# stm32devboard_f103c6.net
KiCad netlist of a schematic drawn in EasyEDA Pro
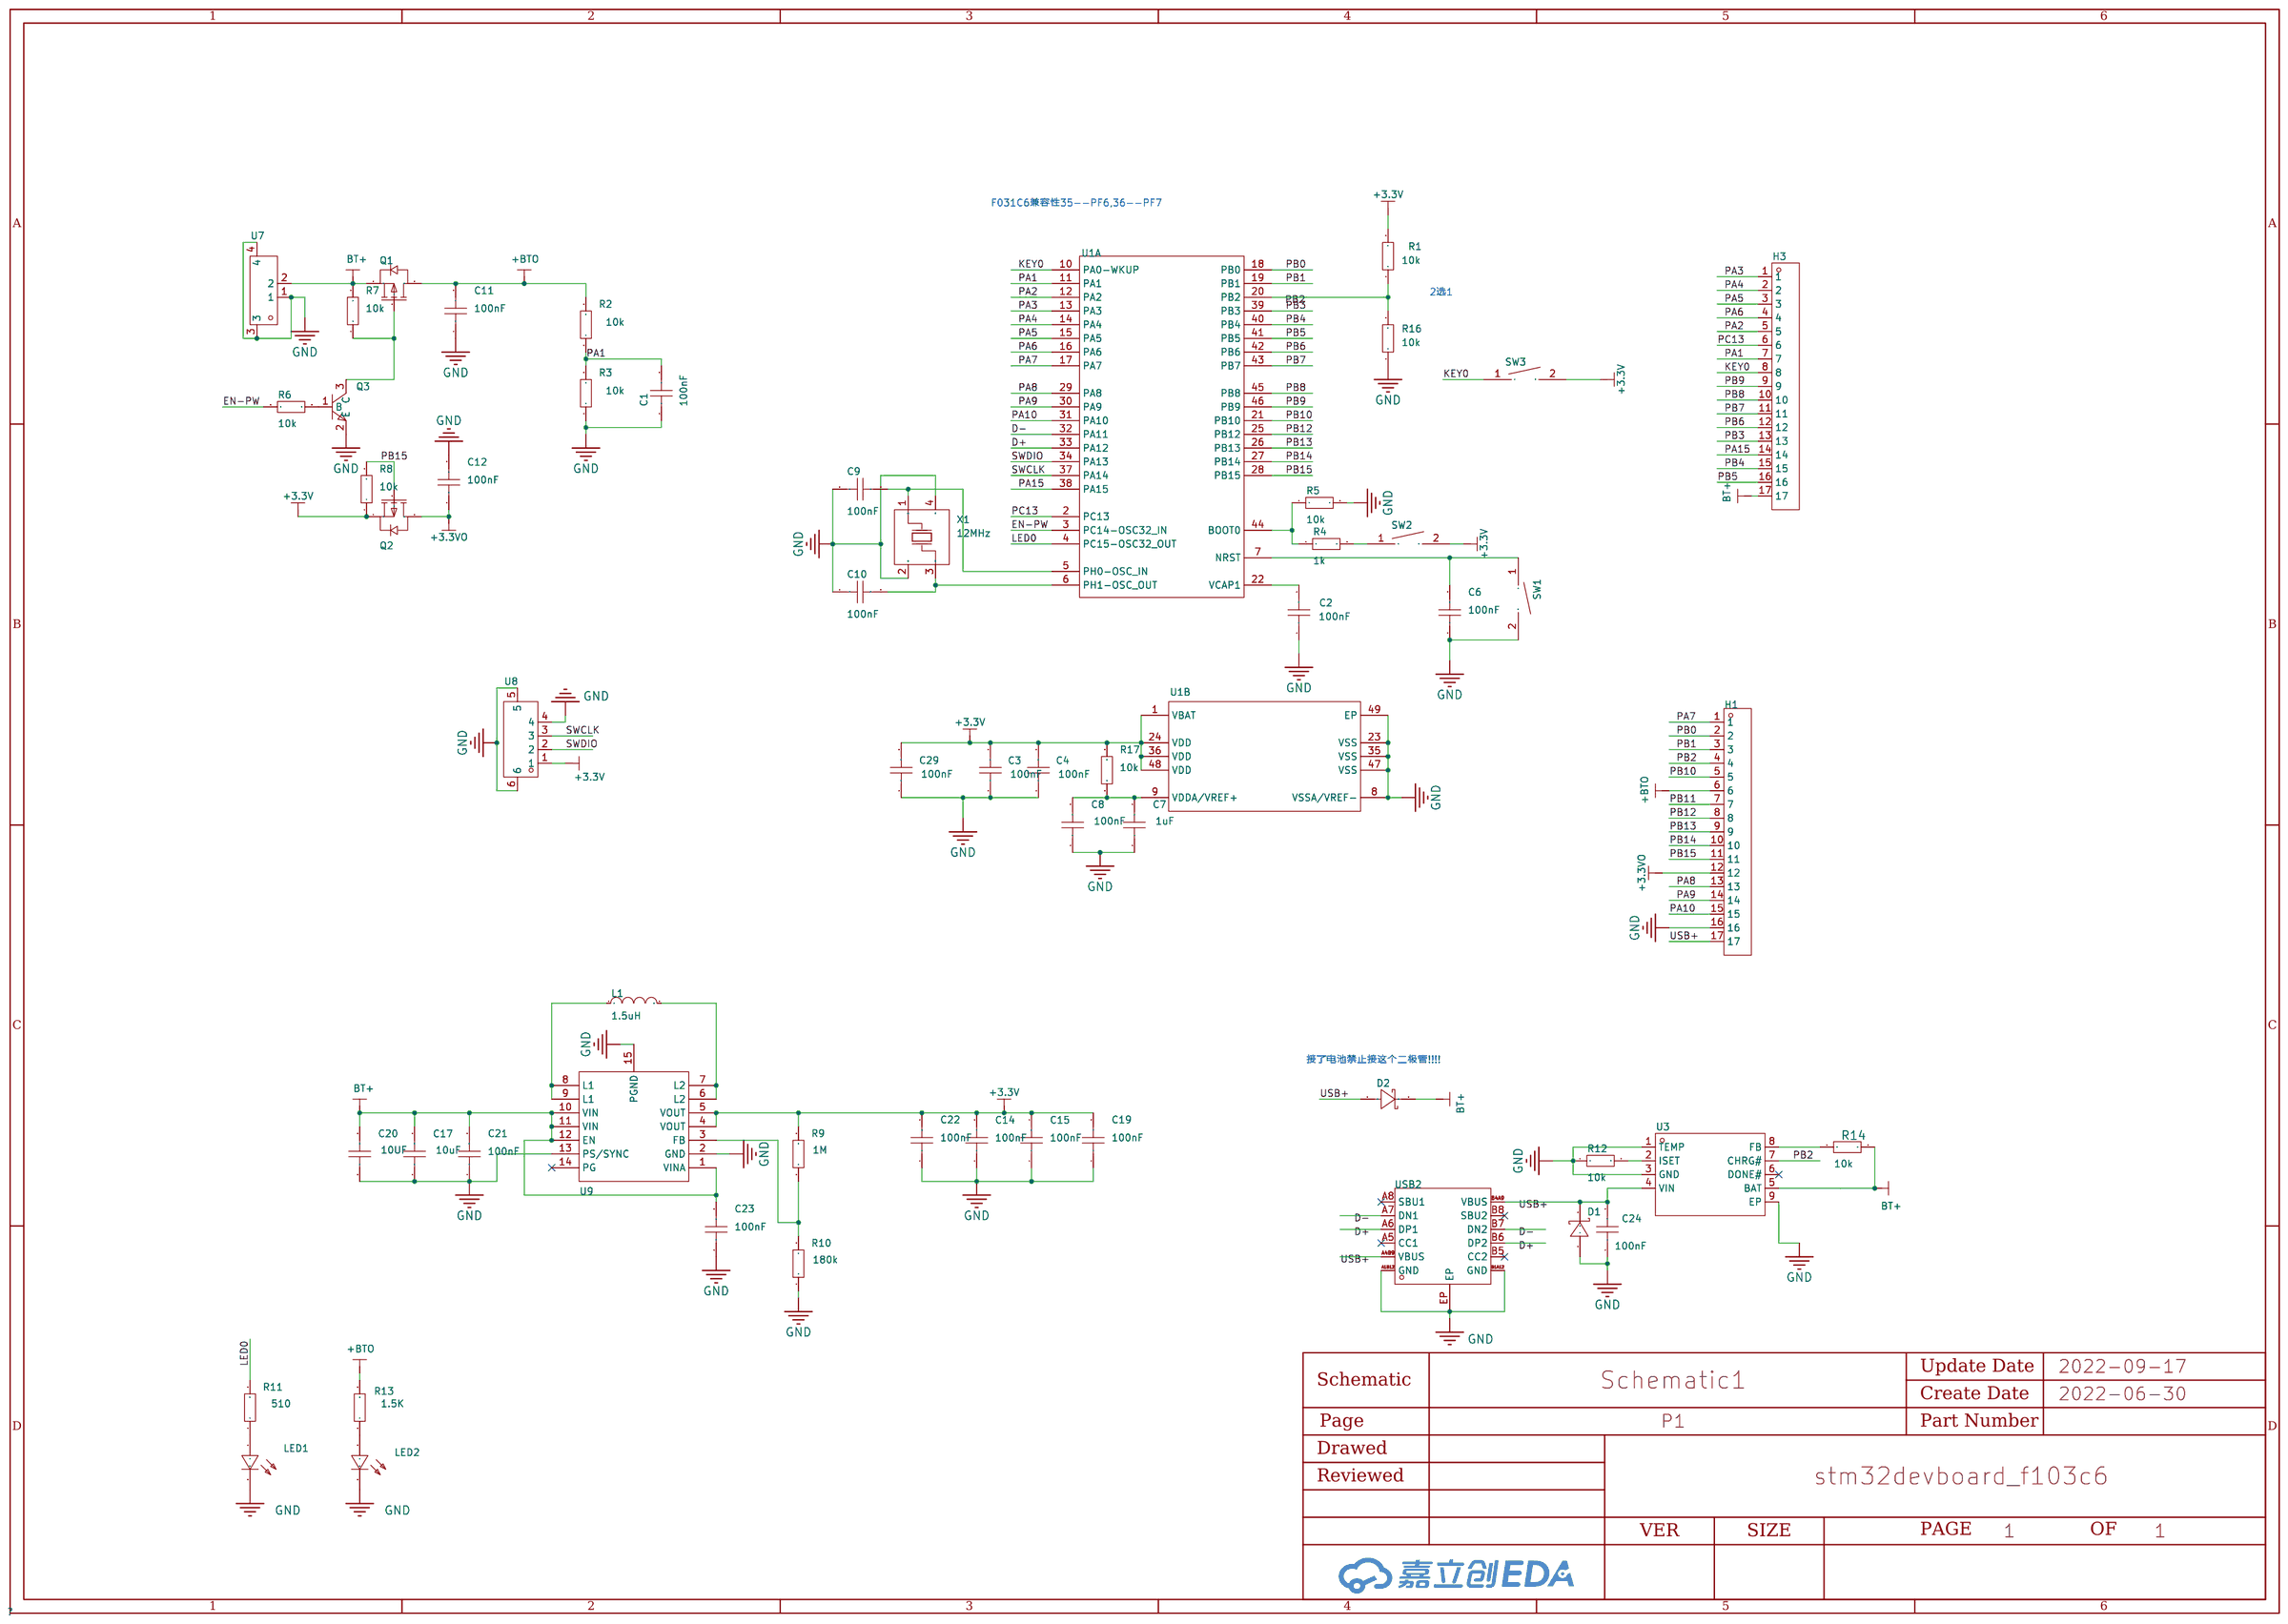
[diagram p0: schematic sheet]

(export (version "E")
  (design (tool "Eeschema 10.0.6"))
  (components
    (comp (ref "C1")
      (value "100nF")
      (footprint "easyedapro:C0402")
      (description "容值:100nF;精度:±10%;额定电压:25V;温度系数:X7R;")
      (fields (field (name "Manufacturer Part") "FN15X104K250PNG") (field (name "Manufacturer") "PSA(信昌电陶)"))
      (libsource (lib "easyedapro") (part "FN15X104K250PNG"))
    )
    (comp (ref "C2")
      (value "100nF")
      (footprint "easyedapro:C0603")
      (description "容值:100nF;精度:±10%;额定电压:50V;温度系数:X7R;")
      (fields
        (field (name "Manufacturer Part") "CC0603KRX7R9BB104")
        (field (name "Manufacturer") "YAGEO(国巨)")
      )
      (libsource (lib "easyedapro") (part "CC0603KRX7R9BB104"))
    )
    (comp (ref "C3")
      (value "100nF")
      (footprint "easyedapro:C0603")
      (description "容值:100nF;精度:±10%;额定电压:50V;温度系数:X7R;")
      (fields
        (field (name "Manufacturer Part") "CC0603KRX7R9BB104")
        (field (name "Manufacturer") "YAGEO(国巨)")
      )
      (libsource (lib "easyedapro") (part "CC0603KRX7R9BB104"))
    )
    (comp (ref "C4")
      (value "100nF")
      (footprint "easyedapro:C0603")
      (description "容值:100nF;精度:±10%;额定电压:50V;温度系数:X7R;")
      (fields
        (field (name "Manufacturer Part") "CC0603KRX7R9BB104")
        (field (name "Manufacturer") "YAGEO(国巨)")
      )
      (libsource (lib "easyedapro") (part "CC0603KRX7R9BB104"))
    )
    (comp (ref "C6")
      (value "100nF")
      (footprint "easyedapro:C0603")
      (description "容值:100nF;精度:±10%;额定电压:50V;温度系数:X7R;")
      (fields
        (field (name "Manufacturer Part") "CC0603KRX7R9BB104")
        (field (name "Manufacturer") "YAGEO(国巨)")
      )
      (libsource (lib "easyedapro") (part "CC0603KRX7R9BB104"))
    )
    (comp (ref "C7")
      (value "1uF")
      (footprint "easyedapro:C0603")
      (description "容值:100nF;精度:±10%;额定电压:50V;温度系数:X7R;")
      (fields
        (field (name "Manufacturer Part") "CC0603KRX7R9BB104")
        (field (name "Manufacturer") "YAGEO(国巨)")
      )
      (libsource (lib "easyedapro") (part "CC0603KRX7R9BB104"))
    )
    (comp (ref "C8")
      (value "100nF")
      (footprint "easyedapro:C0603")
      (description "容值:100nF;精度:±10%;额定电压:50V;温度系数:X7R;")
      (fields
        (field (name "Manufacturer Part") "CC0603KRX7R9BB104")
        (field (name "Manufacturer") "YAGEO(国巨)")
      )
      (libsource (lib "easyedapro") (part "CC0603KRX7R9BB104"))
    )
    (comp (ref "C9")
      (value "100nF")
      (footprint "easyedapro:C0603")
      (description "容值:100nF;精度:±10%;额定电压:50V;温度系数:X7R;")
      (fields
        (field (name "Manufacturer Part") "CC0603KRX7R9BB104")
        (field (name "Manufacturer") "YAGEO(国巨)")
      )
      (libsource (lib "easyedapro") (part "CC0603KRX7R9BB104"))
    )
    (comp (ref "C10")
      (value "100nF")
      (footprint "easyedapro:C0603")
      (description "容值:100nF;精度:±10%;额定电压:50V;温度系数:X7R;")
      (fields
        (field (name "Manufacturer Part") "CC0603KRX7R9BB104")
        (field (name "Manufacturer") "YAGEO(国巨)")
      )
      (libsource (lib "easyedapro") (part "CC0603KRX7R9BB104"))
    )
    (comp (ref "C11")
      (value "100nF")
      (footprint "easyedapro:C0603")
      (description "容值:100nF;精度:±10%;额定电压:50V;温度系数:X7R;")
      (fields
        (field (name "Manufacturer Part") "CC0603KRX7R9BB104")
        (field (name "Manufacturer") "YAGEO(国巨)")
      )
      (libsource (lib "easyedapro") (part "CC0603KRX7R9BB104"))
    )
    (comp (ref "C12")
      (value "100nF")
      (footprint "easyedapro:C0603")
      (description "容值:100nF;精度:±10%;额定电压:50V;温度系数:X7R;")
      (fields
        (field (name "Manufacturer Part") "CC0603KRX7R9BB104")
        (field (name "Manufacturer") "YAGEO(国巨)")
      )
      (libsource (lib "easyedapro") (part "CC0603KRX7R9BB104"))
    )
    (comp (ref "C14")
      (value "100nF")
      (footprint "easyedapro:C0603")
      (description "容值:100nF;精度:±10%;额定电压:50V;温度系数:X7R;")
      (fields
        (field (name "Manufacturer Part") "CC0603KRX7R9BB104")
        (field (name "Manufacturer") "YAGEO(国巨)")
      )
      (libsource (lib "easyedapro") (part "CC0603KRX7R9BB104"))
    )
    (comp (ref "C15")
      (value "100nF")
      (footprint "easyedapro:C0603")
      (description "容值:100nF;精度:±10%;额定电压:50V;温度系数:X7R;")
      (fields
        (field (name "Manufacturer Part") "CC0603KRX7R9BB104")
        (field (name "Manufacturer") "YAGEO(国巨)")
      )
      (libsource (lib "easyedapro") (part "CC0603KRX7R9BB104"))
    )
    (comp (ref "C17")
      (value "10uF")
      (footprint "easyedapro:C0603")
      (description "容值:100nF;精度:±10%;额定电压:50V;温度系数:X7R;")
      (fields
        (field (name "Manufacturer Part") "CC0603KRX7R9BB104")
        (field (name "Manufacturer") "YAGEO(国巨)")
      )
      (libsource (lib "easyedapro") (part "CC0603KRX7R9BB104"))
    )
    (comp (ref "C19")
      (value "100nF")
      (footprint "easyedapro:C0603")
      (description "容值:100nF;精度:±10%;额定电压:50V;温度系数:X7R;")
      (fields
        (field (name "Manufacturer Part") "CC0603KRX7R9BB104")
        (field (name "Manufacturer") "YAGEO(国巨)")
      )
      (libsource (lib "easyedapro") (part "CC0603KRX7R9BB104"))
    )
    (comp (ref "C20")
      (value "10UF")
      (footprint "easyedapro:C0603")
      (description "容值:100nF;精度:±10%;额定电压:50V;温度系数:X7R;")
      (fields
        (field (name "Manufacturer Part") "CC0603KRX7R9BB104")
        (field (name "Manufacturer") "YAGEO(国巨)")
      )
      (libsource (lib "easyedapro") (part "CC0603KRX7R9BB104"))
    )
    (comp (ref "C21")
      (value "100nF")
      (footprint "easyedapro:C0402")
      (description "容值:100nF;精度:±10%;额定电压:25V;温度系数:X7R;")
      (fields (field (name "Manufacturer Part") "FN15X104K250PNG") (field (name "Manufacturer") "PSA(信昌电陶)"))
      (libsource (lib "easyedapro") (part "FN15X104K250PNG"))
    )
    (comp (ref "C22")
      (value "100nF")
      (footprint "easyedapro:C0402")
      (description "容值:100nF;精度:±10%;额定电压:25V;温度系数:X7R;")
      (fields (field (name "Manufacturer Part") "FN15X104K250PNG") (field (name "Manufacturer") "PSA(信昌电陶)"))
      (libsource (lib "easyedapro") (part "FN15X104K250PNG"))
    )
    (comp (ref "C23")
      (value "100nF")
      (footprint "easyedapro:C0603")
      (description "容值:100nF;精度:±10%;额定电压:50V;温度系数:X7R;")
      (fields
        (field (name "Manufacturer Part") "CC0603KRX7R9BB104")
        (field (name "Manufacturer") "YAGEO(国巨)")
      )
      (libsource (lib "easyedapro") (part "CC0603KRX7R9BB104"))
    )
    (comp (ref "C24")
      (value "100nF")
      (footprint "easyedapro:C0603")
      (description "容值:100nF;精度:±10%;额定电压:50V;温度系数:X7R;")
      (fields
        (field (name "Manufacturer Part") "CC0603KRX7R9BB104")
        (field (name "Manufacturer") "YAGEO(国巨)")
      )
      (libsource (lib "easyedapro") (part "CC0603KRX7R9BB104"))
    )
    (comp (ref "C29")
      (value "100nF")
      (footprint "easyedapro:C0402")
      (description "容值:100nF;精度:±10%;额定电压:25V;温度系数:X7R;")
      (fields (field (name "Manufacturer Part") "FN15X104K250PNG") (field (name "Manufacturer") "PSA(信昌电陶)"))
      (libsource (lib "easyedapro") (part "FN15X104K250PNG"))
    )
    (comp (ref "D1")
      (value "~")
      (footprint "easyedapro:SOD-123FL_L2.6-W1.6-LS3.4-R-FD")
      (description "极性:单向;反向截止电压(Vrwm):5V;击穿电压(最小值):6.4V;峰值脉冲电流(Ipp)@10/1000s:21.7A;最大钳位电压:9.4V;")
      (fields (field (name "Manufacturer Part") "SMFJ5.0A") (field (name "Manufacturer") "BORN伯恩半导体"))
      (libsource (lib "easyedapro") (part "SMFJ5.0A_C151893"))
    )
    (comp (ref "D2")
      (value "1N5819WS S4")
      (footprint "easyedapro:SOD-323_L1.6-W1.3-LS2.7-RD")
      (description "二极管配置:独立式;直流反向耐压(Vr):40V;平均整流电流(Io):350mA;正向压降(Vf):600mV@200mA;反向电流(Ir):5A@30V;")
      (fields (field (name "Manufacturer") "JSMSEMI(杰盛微)"))
      (libsource (lib "easyedapro") (part "1N5819WS S4"))
    )
    (comp (ref "H1")
      (value "X6511WV-17H-C30D60")
      (footprint "easyedapro:HDR-TH_17P-P2.54-V-M")
      (fields (field (name "Manufacturer") "XKB Connectivity(中国星坤)"))
      (libsource (lib "easyedapro") (part "X6511WV-17H-C30D60"))
    )
    (comp (ref "H3")
      (value "X6511WV-17H-C30D60")
      (footprint "easyedapro:HDR-TH_17P-P2.54-V-M")
      (fields (field (name "Manufacturer") "XKB Connectivity(中国星坤)"))
      (libsource (lib "easyedapro") (part "X6511WV-17H-C30D60"))
    )
    (comp (ref "L1")
      (value "1.5uH")
      (footprint "easyedapro:IND-SMD_L4.0-W4.0_FNR40XXS")
      (description "电感值:1.5uH;精度:±20%;额定电流:3.34A;直流电阻(DCR):26m;")
      (fields (field (name "Manufacturer Part") "FNR4030S1R5MT") (field (name "Manufacturer") "cjiang(长江微电)"))
      (libsource (lib "easyedapro") (part "FNR4030S1R5MT"))
    )
    (comp (ref "LED1")
      (value "~")
      (footprint "easyedapro:LED0603-R-RD")
      (description "照明颜色:翠绿;色温 - CCT（K）:-;主波长/色坐标:520~535nm;")
      (fields
        (field (name "Manufacturer Part") "19-217/GHC-YR1S2/3T")
        (field (name "Manufacturer") "EVERLIGHT(台湾亿光)")
      )
      (libsource (lib "easyedapro") (part "19-217/GHC-YR1S2/3T"))
    )
    (comp (ref "LED2")
      (value "~")
      (footprint "easyedapro:LED0603-R-RD")
      (description "照明颜色:翠绿;色温 - CCT（K）:-;主波长/色坐标:520~535nm;")
      (fields
        (field (name "Manufacturer Part") "19-217/GHC-YR1S2/3T")
        (field (name "Manufacturer") "EVERLIGHT(台湾亿光)")
      )
      (libsource (lib "easyedapro") (part "19-217/GHC-YR1S2/3T"))
    )
    (comp (ref "Q1")
      (value "~")
      (footprint "easyedapro:SOT-23-3_L2.9-W1.3-P1.90-LS2.4-TR")
      (fields (field (name "Manufacturer Part") "AP2301B") (field (name "Manufacturer") "ALLPOWER(铨力)"))
      (libsource (lib "easyedapro") (part "AP2301B"))
    )
    (comp (ref "Q2")
      (value "~")
      (footprint "easyedapro:SOT-23-3_L2.9-W1.3-P1.90-LS2.4-TR")
      (fields (field (name "Manufacturer Part") "AP2301B") (field (name "Manufacturer") "ALLPOWER(铨力)"))
      (libsource (lib "easyedapro") (part "AP2301B"))
    )
    (comp (ref "Q3")
      (value "~")
      (footprint "easyedapro:SOT-23-3_L2.9-W1.3-P1.90-LS2.4-BR")
      (fields (field (name "Manufacturer Part") "S8050 J3Y") (field (name "Manufacturer") "FOSAN(富信)"))
      (libsource (lib "easyedapro") (part "S8050_C2926165"))
    )
    (comp (ref "R1")
      (value "10k")
      (footprint "easyedapro:R0603")
      (description "电阻类型:薄膜电阻;阻值:10k;精度:±0.1%;功率:100mW;温度系数:±25ppm/;最大工作电压:75V;工作温度范围:-55~+155;")
      (fields
        (field (name "Manufacturer Part") "TR0603B10K0P0525Z")
        (field (name "Manufacturer") "EVER OHMS(天二科技)")
      )
      (libsource (lib "easyedapro") (part "R_0603_EU"))
    )
    (comp (ref "R2")
      (value "10k")
      (footprint "easyedapro:R0603")
      (description "电阻类型:薄膜电阻;阻值:10k;精度:±0.1%;功率:100mW;温度系数:±25ppm/;最大工作电压:75V;工作温度范围:-55~+155;")
      (fields
        (field (name "Manufacturer Part") "TR0603B10K0P0525Z")
        (field (name "Manufacturer") "EVER OHMS(天二科技)")
      )
      (libsource (lib "easyedapro") (part "R_0603_EU"))
    )
    (comp (ref "R3")
      (value "10k")
      (footprint "easyedapro:R0603")
      (description "电阻类型:薄膜电阻;阻值:10k;精度:±0.1%;功率:100mW;温度系数:±25ppm/;最大工作电压:75V;工作温度范围:-55~+155;")
      (fields
        (field (name "Manufacturer Part") "TR0603B10K0P0525Z")
        (field (name "Manufacturer") "EVER OHMS(天二科技)")
      )
      (libsource (lib "easyedapro") (part "R_0603_EU"))
    )
    (comp (ref "R4")
      (value "1k")
      (footprint "easyedapro:R0603")
      (description "电阻类型:薄膜电阻;阻值:10k;精度:±0.1%;功率:100mW;温度系数:±25ppm/;最大工作电压:75V;工作温度范围:-55~+155;")
      (fields
        (field (name "Manufacturer Part") "TR0603B10K0P0525Z")
        (field (name "Manufacturer") "EVER OHMS(天二科技)")
      )
      (libsource (lib "easyedapro") (part "R_0603_EU"))
    )
    (comp (ref "R5")
      (value "10k")
      (footprint "easyedapro:R0603")
      (description "电阻类型:薄膜电阻;阻值:10k;精度:±0.1%;功率:100mW;温度系数:±25ppm/;最大工作电压:75V;工作温度范围:-55~+155;")
      (fields
        (field (name "Manufacturer Part") "TR0603B10K0P0525Z")
        (field (name "Manufacturer") "EVER OHMS(天二科技)")
      )
      (libsource (lib "easyedapro") (part "R_0603_EU"))
    )
    (comp (ref "R6")
      (value "10k")
      (footprint "easyedapro:R0603")
      (description "电阻类型:薄膜电阻;阻值:10k;精度:±0.1%;功率:100mW;温度系数:±25ppm/;最大工作电压:75V;工作温度范围:-55~+155;")
      (fields
        (field (name "Manufacturer Part") "TR0603B10K0P0525Z")
        (field (name "Manufacturer") "EVER OHMS(天二科技)")
      )
      (libsource (lib "easyedapro") (part "R_0603_EU"))
    )
    (comp (ref "R7")
      (value "10k")
      (footprint "easyedapro:R0603")
      (description "电阻类型:薄膜电阻;阻值:10k;精度:±0.1%;功率:100mW;温度系数:±25ppm/;最大工作电压:75V;工作温度范围:-55~+155;")
      (fields
        (field (name "Manufacturer Part") "TR0603B10K0P0525Z")
        (field (name "Manufacturer") "EVER OHMS(天二科技)")
      )
      (libsource (lib "easyedapro") (part "R_0603_EU"))
    )
    (comp (ref "R8")
      (value "10k")
      (footprint "easyedapro:R0603")
      (description "电阻类型:薄膜电阻;阻值:10k;精度:±0.1%;功率:100mW;温度系数:±25ppm/;最大工作电压:75V;工作温度范围:-55~+155;")
      (fields
        (field (name "Manufacturer Part") "TR0603B10K0P0525Z")
        (field (name "Manufacturer") "EVER OHMS(天二科技)")
      )
      (libsource (lib "easyedapro") (part "R_0603_EU"))
    )
    (comp (ref "R9")
      (value "1M")
      (footprint "easyedapro:R0603")
      (description "电阻类型:薄膜电阻;阻值:10k;精度:±0.1%;功率:100mW;温度系数:±25ppm/;最大工作电压:75V;工作温度范围:-55~+155;")
      (fields
        (field (name "Manufacturer Part") "TR0603B10K0P0525Z")
        (field (name "Manufacturer") "EVER OHMS(天二科技)")
      )
      (libsource (lib "easyedapro") (part "R_0603_EU"))
    )
    (comp (ref "R10")
      (value "180k")
      (footprint "easyedapro:R0603")
      (description "电阻类型:薄膜电阻;阻值:10k;精度:±0.1%;功率:100mW;温度系数:±25ppm/;最大工作电压:75V;工作温度范围:-55~+155;")
      (fields
        (field (name "Manufacturer Part") "TR0603B10K0P0525Z")
        (field (name "Manufacturer") "EVER OHMS(天二科技)")
      )
      (libsource (lib "easyedapro") (part "R_0603_EU"))
    )
    (comp (ref "R11")
      (value "510")
      (footprint "easyedapro:R0603")
      (description "电阻类型:薄膜电阻;阻值:10k;精度:±0.1%;功率:100mW;温度系数:±25ppm/;最大工作电压:75V;工作温度范围:-55~+155;")
      (fields
        (field (name "Manufacturer Part") "TR0603B10K0P0525Z")
        (field (name "Manufacturer") "EVER OHMS(天二科技)")
      )
      (libsource (lib "easyedapro") (part "R_0603_EU"))
    )
    (comp (ref "R12")
      (value "10k")
      (footprint "easyedapro:R0603")
      (description "电阻类型:薄膜电阻;阻值:10k;精度:±0.1%;功率:100mW;温度系数:±25ppm/;最大工作电压:75V;工作温度范围:-55~+155;")
      (fields
        (field (name "Manufacturer Part") "TR0603B10K0P0525Z")
        (field (name "Manufacturer") "EVER OHMS(天二科技)")
      )
      (libsource (lib "easyedapro") (part "R_0603_EU"))
    )
    (comp (ref "R13")
      (value "1.5K")
      (footprint "easyedapro:R0603")
      (description "电阻类型:薄膜电阻;阻值:10k;精度:±0.1%;功率:100mW;温度系数:±25ppm/;最大工作电压:75V;工作温度范围:-55~+155;")
      (fields
        (field (name "Manufacturer Part") "TR0603B10K0P0525Z")
        (field (name "Manufacturer") "EVER OHMS(天二科技)")
      )
      (libsource (lib "easyedapro") (part "R_0603_EU"))
    )
    (comp (ref "R14")
      (value "10k")
      (footprint "easyedapro:R0603_1")
      (description "阻值:10k;精度:±0.1%;温度系数:±25ppm/;功率:100mW;工作温度范围:-55~+155;电阻类型:薄膜电阻;最大工作电压:75V;")
      (fields
        (field (name "Manufacturer Part") "TR0603B10K0P0525Z")
        (field (name "Manufacturer") "EVER OHMS(天二科技)")
      )
      (libsource (lib "easyedapro") (part "TR0603B10KP05250.1W"))
    )
    (comp (ref "R16")
      (value "10k")
      (footprint "easyedapro:R0603")
      (description "电阻类型:薄膜电阻;阻值:10k;精度:±0.1%;功率:100mW;温度系数:±25ppm/;最大工作电压:75V;工作温度范围:-55~+155;")
      (fields
        (field (name "Manufacturer Part") "TR0603B10K0P0525Z")
        (field (name "Manufacturer") "EVER OHMS(天二科技)")
      )
      (libsource (lib "easyedapro") (part "R_0603_EU"))
    )
    (comp (ref "R17")
      (value "10k")
      (footprint "easyedapro:R0603")
      (description "电阻类型:薄膜电阻;阻值:10k;精度:±0.1%;功率:100mW;温度系数:±25ppm/;最大工作电压:75V;工作温度范围:-55~+155;")
      (fields
        (field (name "Manufacturer Part") "TR0603B10K0P0525Z")
        (field (name "Manufacturer") "EVER OHMS(天二科技)")
      )
      (libsource (lib "easyedapro") (part "R_0603_EU"))
    )
    (comp (ref "SW1")
      (value "TSA343G00-250J2")
      (footprint "easyedapro:SW-SMD_L4.0-W2.9-LS5.0")
      (fields (field (name "Manufacturer") "BRIGHT(博瑞泰)"))
      (libsource (lib "easyedapro") (part "TSA343G00-250J2"))
    )
    (comp (ref "SW2")
      (value "TSA343G00-250J2")
      (footprint "easyedapro:SW-SMD_L4.0-W2.9-LS5.0")
      (fields (field (name "Manufacturer") "BRIGHT(博瑞泰)"))
      (libsource (lib "easyedapro") (part "TSA343G00-250J2"))
    )
    (comp (ref "SW3")
      (value "TSA343G00-250J2")
      (footprint "easyedapro:SW-SMD_L4.0-W2.9-LS5.0")
      (fields (field (name "Manufacturer") "BRIGHT(博瑞泰)"))
      (libsource (lib "easyedapro") (part "TSA343G00-250J2"))
    )
    (comp (ref "U1")
      (value "STM32F401CCU6")
      (footprint "easyedapro:UFQFPN-48_L7.0-W7.0-P0.50-BL-EP")
      (description "主频（MAX):84MHz;工作电压:1.7V ~ 3.6V;")
      (fields (field (name "Manufacturer") "ST(意法半导体)"))
      (libsource (lib "easyedapro") (part "STM32F401CCU6"))
    )
    (comp (ref "U3")
      (value "CN3058E")
      (footprint "easyedapro:SOIC-8_L4.9-W3.9-P1.27-LS6.0-BL-EP3.3_1")
      (description "充电电池的类型:-;电池单元组数:-;最大充电电流:-;充满的电池组电压:-;最大供应电压:-;")
      (fields (field (name "Manufacturer") "CONSONANCE(上海如韵)"))
      (libsource (lib "easyedapro") (part "CN3058E"))
    )
    (comp (ref "U7")
      (value "~")
      (footprint "easyedapro:CONN-SMD_2P-P1.25_GH1.25-2P")
      (fields
        (field (name "Manufacturer Part") "GH1.25-2PLTPZ")
        (field (name "Manufacturer") "BOOMELE(博穆精密)")
      )
      (libsource (lib "easyedapro") (part "GH1.25-2PLTPZ"))
    )
    (comp (ref "U8")
      (value "WAFER-GH1.25-4PLB")
      (footprint "easyedapro:CONN-TH_4P-P1.25_XUNPU_WAFER-GH1.25-4PLB")
      (description "参考系列:GH;间距:1.25mm;插针结构:1x4P;排数:1;每排PIN数:4;公母:公型插针;安装方式:立贴;额定电流:1A;工作温度范围:-25°C~+85°C;")
      (fields (field (name "Manufacturer") "XUNPU(讯普)"))
      (libsource (lib "easyedapro") (part "WAFER-GH1.25-4PLB"))
    )
    (comp (ref "U9")
      (value "~")
      (footprint "easyedapro:VSON-14_L4.0-W3.0-P0.50-BL-EP_TI_DSJ")
      (description "功能类型:升降压型;同步整流:是;输出通道数:1;拓扑结构:降压-升压式;输入电压:1.8V~5.5V;输出电压:1.2V~5.5V;输出电流(最大值):3.5A;开关频率:2.4MHz;")
      (fields (field (name "Manufacturer Part") "TPS63020DSJR") (field (name "Manufacturer") "TI(德州仪器)"))
      (libsource (lib "easyedapro") (part "TPS63020DSJR"))
    )
    (comp (ref "USB2")
      (value "TYPEC-304-ACP16")
      (footprint "easyedapro:USB-C-SMD_TYPE-C-16P-1_1")
      (description "连接器类型:Type-C;公母:母座;触点数量:16;端口数量:1;安装方式:卧贴;额定电流 - 电源:3A;工作温度范围:-40~+85;")
      (fields (field (name "Manufacturer") "XUNPU(讯普)"))
      (libsource (lib "easyedapro") (part "TYPEC-304-ACP16"))
    )
    (comp (ref "X1")
      (value "12MHz")
      (footprint "easyedapro:OSC-SMD_4P-L3.2-W2.5-BL_1")
      (description "晶振类型:贴片无源晶振;频率:12MHz;频率公差:±10ppm;频率稳定度:±30ppm;负载电容:20pF;工作温度:-40~+85;")
      (fields (field (name "Manufacturer Part") "X322512MSB4SI") (field (name "Manufacturer") "YXC扬兴科技"))
      (libsource (lib "easyedapro") (part "X322512MSB4SI"))
    )
  )
  (nets
    (net (code "1") (name "+3.3V") (class "Default")
      (node (ref "C14") (pin "2") (pinfunction "2_2") (pintype "input"))
      (node (ref "C15") (pin "2") (pinfunction "2_2") (pintype "input"))
      (node (ref "C19") (pin "2") (pinfunction "2_2") (pintype "input"))
      (node (ref "C22") (pin "2") (pinfunction "2_2") (pintype "input"))
      (node (ref "C29") (pin "2") (pinfunction "2_2") (pintype "input"))
      (node (ref "C3") (pin "2") (pinfunction "2_2") (pintype "input"))
      (node (ref "C4") (pin "2") (pinfunction "2_2") (pintype "input"))
      (node (ref "Q2") (pin "1") (pinfunction "S_1") (pintype "input"))
      (node (ref "R1") (pin "2") (pinfunction "2_2") (pintype "input"))
      (node (ref "R17") (pin "2") (pinfunction "2_2") (pintype "input"))
      (node (ref "R8") (pin "1") (pinfunction "1_1") (pintype "input"))
      (node (ref "R9") (pin "2") (pinfunction "2_2") (pintype "input"))
      (node (ref "SW2") (pin "2") (pinfunction "2_2") (pintype "input"))
      (node (ref "SW3") (pin "2") (pinfunction "2_2") (pintype "input"))
      (node (ref "U1") (pin "1") (pinfunction "VBAT_1") (pintype "input"))
      (node (ref "U1") (pin "24") (pinfunction "VDD_24") (pintype "input"))
      (node (ref "U1") (pin "36") (pinfunction "VDD_36") (pintype "input"))
      (node (ref "U1") (pin "48") (pinfunction "VDD_48") (pintype "input"))
      (node (ref "U8") (pin "1") (pinfunction "1_1") (pintype "input"))
      (node (ref "U9") (pin "4") (pinfunction "VOUT_4") (pintype "input"))
      (node (ref "U9") (pin "5") (pinfunction "VOUT_5") (pintype "input"))
    )
    (net (code "2") (name "+3.3VO") (class "Default")
      (node (ref "C12") (pin "1") (pinfunction "1_1") (pintype "input"))
      (node (ref "H1") (pin "12") (pinfunction "12_12") (pintype "input"))
      (node (ref "Q2") (pin "3") (pinfunction "D_3") (pintype "input"))
    )
    (net (code "3") (name "+BTO") (class "Default")
      (node (ref "C11") (pin "2") (pinfunction "2_2") (pintype "input"))
      (node (ref "H1") (pin "6") (pinfunction "6_6") (pintype "input"))
      (node (ref "Q1") (pin "3") (pinfunction "D_3") (pintype "input"))
      (node (ref "R13") (pin "2") (pinfunction "2_2") (pintype "input"))
      (node (ref "R2") (pin "2") (pinfunction "2_2") (pintype "input"))
    )
    (net (code "4") (name "/D+") (class "Default")
      (node (ref "U1") (pin "33") (pinfunction "PA12_33") (pintype "bidirectional"))
      (node (ref "USB2") (pin "A6") (pinfunction "DP1_A6") (pintype "input"))
      (node (ref "USB2") (pin "B6") (pinfunction "DP2_B6") (pintype "input"))
    )
    (net (code "5") (name "/D-") (class "Default")
      (node (ref "U1") (pin "32") (pinfunction "PA11_32") (pintype "bidirectional"))
      (node (ref "USB2") (pin "A7") (pinfunction "DN1_A7") (pintype "input"))
      (node (ref "USB2") (pin "B7") (pinfunction "DN2_B7") (pintype "input"))
    )
    (net (code "6") (name "/EN-PW") (class "Default")
      (node (ref "R6") (pin "1") (pinfunction "1_1") (pintype "input"))
      (node (ref "U1") (pin "3") (pinfunction "PC14-OSC32_IN_3") (pintype "bidirectional"))
    )
    (net (code "7") (name "/KEY0") (class "Default")
      (node (ref "H3") (pin "8") (pinfunction "8_8") (pintype "input"))
      (node (ref "SW3") (pin "1") (pinfunction "1_1") (pintype "input"))
      (node (ref "U1") (pin "10") (pinfunction "PA0-WKUP_10") (pintype "bidirectional"))
    )
    (net (code "8") (name "/LED0") (class "Default")
      (node (ref "R11") (pin "2") (pinfunction "2_2") (pintype "input"))
      (node (ref "U1") (pin "4") (pinfunction "PC15-OSC32_OUT_4") (pintype "bidirectional"))
    )
    (net (code "9") (name "/PA1") (class "Default")
      (node (ref "C1") (pin "2") (pinfunction "2_2") (pintype "input"))
      (node (ref "H3") (pin "7") (pinfunction "7_7") (pintype "input"))
      (node (ref "R2") (pin "1") (pinfunction "1_1") (pintype "input"))
      (node (ref "R3") (pin "2") (pinfunction "2_2") (pintype "input"))
      (node (ref "U1") (pin "11") (pinfunction "PA1_11") (pintype "bidirectional"))
    )
    (net (code "10") (name "/PA2") (class "Default")
      (node (ref "H3") (pin "5") (pinfunction "5_5") (pintype "input"))
      (node (ref "U1") (pin "12") (pinfunction "PA2_12") (pintype "bidirectional"))
    )
    (net (code "11") (name "/PA3") (class "Default")
      (node (ref "H3") (pin "1") (pinfunction "1_1") (pintype "input"))
      (node (ref "U1") (pin "13") (pinfunction "PA3_13") (pintype "bidirectional"))
    )
    (net (code "12") (name "/PA4") (class "Default")
      (node (ref "H3") (pin "2") (pinfunction "2_2") (pintype "input"))
      (node (ref "U1") (pin "14") (pinfunction "PA4_14") (pintype "bidirectional"))
    )
    (net (code "13") (name "/PA5") (class "Default")
      (node (ref "H3") (pin "3") (pinfunction "3_3") (pintype "input"))
      (node (ref "U1") (pin "15") (pinfunction "PA5_15") (pintype "bidirectional"))
    )
    (net (code "14") (name "/PA6") (class "Default")
      (node (ref "H3") (pin "4") (pinfunction "4_4") (pintype "input"))
      (node (ref "U1") (pin "16") (pinfunction "PA6_16") (pintype "bidirectional"))
    )
    (net (code "15") (name "/PA7") (class "Default")
      (node (ref "H1") (pin "1") (pinfunction "1_1") (pintype "input"))
      (node (ref "U1") (pin "17") (pinfunction "PA7_17") (pintype "bidirectional"))
    )
    (net (code "16") (name "/PA8") (class "Default")
      (node (ref "H1") (pin "13") (pinfunction "13_13") (pintype "input"))
      (node (ref "U1") (pin "29") (pinfunction "PA8_29") (pintype "bidirectional"))
    )
    (net (code "17") (name "/PA9") (class "Default")
      (node (ref "H1") (pin "14") (pinfunction "14_14") (pintype "input"))
      (node (ref "U1") (pin "30") (pinfunction "PA9_30") (pintype "bidirectional"))
    )
    (net (code "18") (name "/PA10") (class "Default")
      (node (ref "H1") (pin "15") (pinfunction "15_15") (pintype "input"))
      (node (ref "U1") (pin "31") (pinfunction "PA10_31") (pintype "bidirectional"))
    )
    (net (code "19") (name "/PA15") (class "Default")
      (node (ref "H3") (pin "14") (pinfunction "14_14") (pintype "input"))
      (node (ref "U1") (pin "38") (pinfunction "PA15_38") (pintype "bidirectional"))
    )
    (net (code "20") (name "/PB0") (class "Default")
      (node (ref "H1") (pin "2") (pinfunction "2_2") (pintype "input"))
      (node (ref "U1") (pin "18") (pinfunction "PB0_18") (pintype "bidirectional"))
    )
    (net (code "21") (name "/PB1") (class "Default")
      (node (ref "H1") (pin "3") (pinfunction "3_3") (pintype "input"))
      (node (ref "U1") (pin "19") (pinfunction "PB1_19") (pintype "bidirectional"))
    )
    (net (code "22") (name "/PB2") (class "Default")
      (node (ref "H1") (pin "4") (pinfunction "4_4") (pintype "input"))
      (node (ref "R1") (pin "1") (pinfunction "1_1") (pintype "input"))
      (node (ref "R16") (pin "2") (pinfunction "2_2") (pintype "input"))
      (node (ref "U1") (pin "20") (pinfunction "PB2_20") (pintype "bidirectional"))
      (node (ref "U3") (pin "7") (pinfunction "CHRG#_7") (pintype "input"))
    )
    (net (code "23") (name "/PB3") (class "Default")
      (node (ref "H3") (pin "13") (pinfunction "13_13") (pintype "input"))
      (node (ref "U1") (pin "39") (pinfunction "PB3_39") (pintype "bidirectional"))
    )
    (net (code "24") (name "/PB4") (class "Default")
      (node (ref "H3") (pin "15") (pinfunction "15_15") (pintype "input"))
      (node (ref "U1") (pin "40") (pinfunction "PB4_40") (pintype "bidirectional"))
    )
    (net (code "25") (name "/PB5") (class "Default")
      (node (ref "H3") (pin "16") (pinfunction "16_16") (pintype "input"))
      (node (ref "U1") (pin "41") (pinfunction "PB5_41") (pintype "bidirectional"))
    )
    (net (code "26") (name "/PB6") (class "Default")
      (node (ref "H3") (pin "12") (pinfunction "12_12") (pintype "input"))
      (node (ref "U1") (pin "42") (pinfunction "PB6_42") (pintype "bidirectional"))
    )
    (net (code "27") (name "/PB7") (class "Default")
      (node (ref "H3") (pin "11") (pinfunction "11_11") (pintype "input"))
      (node (ref "U1") (pin "43") (pinfunction "PB7_43") (pintype "bidirectional"))
    )
    (net (code "28") (name "/PB8") (class "Default")
      (node (ref "H3") (pin "10") (pinfunction "10_10") (pintype "input"))
      (node (ref "U1") (pin "45") (pinfunction "PB8_45") (pintype "bidirectional"))
    )
    (net (code "29") (name "/PB9") (class "Default")
      (node (ref "H3") (pin "9") (pinfunction "9_9") (pintype "input"))
      (node (ref "U1") (pin "46") (pinfunction "PB9_46") (pintype "bidirectional"))
    )
    (net (code "30") (name "/PB10") (class "Default")
      (node (ref "H1") (pin "5") (pinfunction "5_5") (pintype "input"))
      (node (ref "U1") (pin "21") (pinfunction "PB10_21") (pintype "bidirectional"))
    )
    (net (code "31") (name "/PB11") (class "Default")
      (node (ref "H1") (pin "7") (pinfunction "7_7") (pintype "input"))
    )
    (net (code "32") (name "/PB12") (class "Default")
      (node (ref "H1") (pin "8") (pinfunction "8_8") (pintype "input"))
      (node (ref "U1") (pin "25") (pinfunction "PB12_25") (pintype "bidirectional"))
    )
    (net (code "33") (name "/PB13") (class "Default")
      (node (ref "H1") (pin "9") (pinfunction "9_9") (pintype "input"))
      (node (ref "U1") (pin "26") (pinfunction "PB13_26") (pintype "bidirectional"))
    )
    (net (code "34") (name "/PB14") (class "Default")
      (node (ref "H1") (pin "10") (pinfunction "10_10") (pintype "input"))
      (node (ref "U1") (pin "27") (pinfunction "PB14_27") (pintype "bidirectional"))
    )
    (net (code "35") (name "/PB15") (class "Default")
      (node (ref "H1") (pin "11") (pinfunction "11_11") (pintype "input"))
      (node (ref "Q2") (pin "2") (pinfunction "G_2") (pintype "input"))
      (node (ref "R8") (pin "2") (pinfunction "2_2") (pintype "input"))
      (node (ref "U1") (pin "28") (pinfunction "PB15_28") (pintype "bidirectional"))
    )
    (net (code "36") (name "/PC13") (class "Default")
      (node (ref "H3") (pin "6") (pinfunction "6_6") (pintype "input"))
      (node (ref "U1") (pin "2") (pinfunction "PC13_2") (pintype "bidirectional"))
    )
    (net (code "37") (name "/SWCLK") (class "Default")
      (node (ref "U1") (pin "37") (pinfunction "PA14_37") (pintype "bidirectional"))
      (node (ref "U8") (pin "3") (pinfunction "3_3") (pintype "input"))
    )
    (net (code "38") (name "/SWDIO") (class "Default")
      (node (ref "U1") (pin "34") (pinfunction "PA13_34") (pintype "bidirectional"))
      (node (ref "U8") (pin "2") (pinfunction "2_2") (pintype "input"))
    )
    (net (code "39") (name "/USB+") (class "Default")
      (node (ref "C24") (pin "2") (pinfunction "2_2") (pintype "input"))
      (node (ref "D1") (pin "1") (pinfunction "K_1") (pintype "input"))
      (node (ref "D2") (pin "2") (pinfunction "A_2") (pintype "input"))
      (node (ref "H1") (pin "17") (pinfunction "17_17") (pintype "input"))
      (node (ref "U3") (pin "4") (pinfunction "VIN_4") (pintype "input"))
      (node (ref "USB2") (pin "A4B9") (pinfunction "VBUS_A4B9") (pintype "input"))
      (node (ref "USB2") (pin "B4A9") (pinfunction "VBUS_B4A9") (pintype "input"))
    )
    (net (code "40") (name "BT+") (class "Default")
      (node (ref "C17") (pin "2") (pinfunction "2_2") (pintype "input"))
      (node (ref "C20") (pin "2") (pinfunction "2_2") (pintype "input"))
      (node (ref "C21") (pin "2") (pinfunction "2_2") (pintype "input"))
      (node (ref "C23") (pin "2") (pinfunction "2_2") (pintype "input"))
      (node (ref "D2") (pin "1") (pinfunction "C_1") (pintype "input"))
      (node (ref "H3") (pin "17") (pinfunction "17_17") (pintype "input"))
      (node (ref "Q1") (pin "1") (pinfunction "S_1") (pintype "input"))
      (node (ref "R14") (pin "2") (pinfunction "2_2") (pintype "unspecified"))
      (node (ref "R7") (pin "2") (pinfunction "2_2") (pintype "input"))
      (node (ref "U3") (pin "5") (pinfunction "BAT_5") (pintype "input"))
      (node (ref "U7") (pin "2") (pinfunction "2_2") (pintype "input"))
      (node (ref "U9") (pin "1") (pinfunction "VINA_1") (pintype "input"))
      (node (ref "U9") (pin "10") (pinfunction "VIN_10") (pintype "input"))
      (node (ref "U9") (pin "11") (pinfunction "VIN_11") (pintype "input"))
      (node (ref "U9") (pin "12") (pinfunction "EN_12") (pintype "input"))
    )
    (net (code "41") (name "GND") (class "Default")
      (node (ref "C1") (pin "1") (pinfunction "1_1") (pintype "input"))
      (node (ref "C10") (pin "1") (pinfunction "1_1") (pintype "input"))
      (node (ref "C11") (pin "1") (pinfunction "1_1") (pintype "input"))
      (node (ref "C12") (pin "2") (pinfunction "2_2") (pintype "input"))
      (node (ref "C14") (pin "1") (pinfunction "1_1") (pintype "input"))
      (node (ref "C15") (pin "1") (pinfunction "1_1") (pintype "input"))
      (node (ref "C17") (pin "1") (pinfunction "1_1") (pintype "input"))
      (node (ref "C19") (pin "1") (pinfunction "1_1") (pintype "input"))
      (node (ref "C2") (pin "1") (pinfunction "1_1") (pintype "input"))
      (node (ref "C20") (pin "1") (pinfunction "1_1") (pintype "input"))
      (node (ref "C21") (pin "1") (pinfunction "1_1") (pintype "input"))
      (node (ref "C22") (pin "1") (pinfunction "1_1") (pintype "input"))
      (node (ref "C23") (pin "1") (pinfunction "1_1") (pintype "input"))
      (node (ref "C24") (pin "1") (pinfunction "1_1") (pintype "input"))
      (node (ref "C29") (pin "1") (pinfunction "1_1") (pintype "input"))
      (node (ref "C3") (pin "1") (pinfunction "1_1") (pintype "input"))
      (node (ref "C4") (pin "1") (pinfunction "1_1") (pintype "input"))
      (node (ref "C6") (pin "1") (pinfunction "1_1") (pintype "input"))
      (node (ref "C7") (pin "1") (pinfunction "1_1") (pintype "input"))
      (node (ref "C8") (pin "1") (pinfunction "1_1") (pintype "input"))
      (node (ref "C9") (pin "1") (pinfunction "1_1") (pintype "input"))
      (node (ref "D1") (pin "2") (pinfunction "A_2") (pintype "input"))
      (node (ref "H1") (pin "16") (pinfunction "16_16") (pintype "input"))
      (node (ref "LED1") (pin "2") (pinfunction "C_2") (pintype "input"))
      (node (ref "LED2") (pin "2") (pinfunction "C_2") (pintype "input"))
      (node (ref "Q3") (pin "2") (pinfunction "E_2") (pintype "input"))
      (node (ref "R10") (pin "1") (pinfunction "1_1") (pintype "input"))
      (node (ref "R12") (pin "1") (pinfunction "1_1") (pintype "input"))
      (node (ref "R16") (pin "1") (pinfunction "1_1") (pintype "input"))
      (node (ref "R3") (pin "1") (pinfunction "1_1") (pintype "input"))
      (node (ref "R5") (pin "2") (pinfunction "2_2") (pintype "input"))
      (node (ref "SW1") (pin "2") (pinfunction "2_2") (pintype "input"))
      (node (ref "U1") (pin "23") (pinfunction "VSS_23") (pintype "input"))
      (node (ref "U1") (pin "35") (pinfunction "VSS_35") (pintype "input"))
      (node (ref "U1") (pin "47") (pinfunction "VSS_47") (pintype "input"))
      (node (ref "U1") (pin "49") (pinfunction "EP_49") (pintype "input"))
      (node (ref "U1") (pin "8") (pinfunction "VSSA/VREF-_8") (pintype "input"))
      (node (ref "U3") (pin "1") (pinfunction "TEMP_1") (pintype "input"))
      (node (ref "U3") (pin "3") (pinfunction "GND_3") (pintype "input"))
      (node (ref "U3") (pin "9") (pinfunction "EP_9") (pintype "input"))
      (node (ref "U7") (pin "1") (pinfunction "1_1") (pintype "input"))
      (node (ref "U7") (pin "3") (pinfunction "3_3") (pintype "input"))
      (node (ref "U7") (pin "4") (pinfunction "4_4") (pintype "input"))
      (node (ref "U8") (pin "4") (pinfunction "4_4") (pintype "input"))
      (node (ref "U8") (pin "5") (pinfunction "5_5") (pintype "input"))
      (node (ref "U8") (pin "6") (pinfunction "6_6") (pintype "input"))
      (node (ref "U9") (pin "13") (pinfunction "PS/SYNC_13") (pintype "input"))
      (node (ref "U9") (pin "15") (pinfunction "PGND_15") (pintype "input"))
      (node (ref "U9") (pin "2") (pinfunction "GND_2") (pintype "input"))
      (node (ref "USB2") (pin "A1B12") (pinfunction "GND_A1B12") (pintype "input"))
      (node (ref "USB2") (pin "B1A12") (pinfunction "GND_B1A12") (pintype "input"))
      (node (ref "USB2") (pin "EP") (pinfunction "EP_EP") (pintype "input"))
      (node (ref "X1") (pin "2") (pinfunction "GND_2") (pintype "input"))
      (node (ref "X1") (pin "4") (pinfunction "GND_4") (pintype "input"))
    )
    (net (code "42") (name "Net-(L1-Pad1)") (class "Default")
      (node (ref "L1") (pin "1") (pinfunction "1_1") (pintype "input"))
      (node (ref "U9") (pin "8") (pinfunction "L1_8") (pintype "input"))
      (node (ref "U9") (pin "9") (pinfunction "L1_9") (pintype "input"))
    )
    (net (code "43") (name "Net-(L1-Pad2)") (class "Default")
      (node (ref "L1") (pin "2") (pinfunction "2_2") (pintype "input"))
      (node (ref "U9") (pin "6") (pinfunction "L2_6") (pintype "input"))
      (node (ref "U9") (pin "7") (pinfunction "L2_7") (pintype "input"))
    )
    (net (code "44") (name "Net-(LED1-A)") (class "Default")
      (node (ref "LED1") (pin "1") (pinfunction "A_1") (pintype "input"))
      (node (ref "R11") (pin "1") (pinfunction "1_1") (pintype "input"))
    )
    (net (code "45") (name "Net-(LED2-A)") (class "Default")
      (node (ref "LED2") (pin "1") (pinfunction "A_1") (pintype "input"))
      (node (ref "R13") (pin "1") (pinfunction "1_1") (pintype "input"))
    )
    (net (code "46") (name "Net-(Q1-G)") (class "Default")
      (node (ref "Q1") (pin "2") (pinfunction "G_2") (pintype "input"))
      (node (ref "Q3") (pin "3") (pinfunction "C_3") (pintype "input"))
      (node (ref "R7") (pin "1") (pinfunction "1_1") (pintype "input"))
    )
    (net (code "47") (name "Net-(Q3-B)") (class "Default")
      (node (ref "Q3") (pin "1") (pinfunction "B_1") (pintype "input"))
      (node (ref "R6") (pin "2") (pinfunction "2_2") (pintype "input"))
    )
    (net (code "48") (name "Net-(R4-Pad2)") (class "Default")
      (node (ref "R4") (pin "2") (pinfunction "2_2") (pintype "input"))
      (node (ref "SW2") (pin "1") (pinfunction "1_1") (pintype "input"))
    )
    (net (code "49") (name "Net-(U1A-BOOT0)") (class "Default")
      (node (ref "R4") (pin "1") (pinfunction "1_1") (pintype "input"))
      (node (ref "R5") (pin "1") (pinfunction "1_1") (pintype "input"))
      (node (ref "U1") (pin "44") (pinfunction "BOOT0_44") (pintype "input"))
    )
    (net (code "50") (name "Net-(U1A-NRST)") (class "Default")
      (node (ref "C6") (pin "2") (pinfunction "2_2") (pintype "input"))
      (node (ref "SW1") (pin "1") (pinfunction "1_1") (pintype "input"))
      (node (ref "U1") (pin "7") (pinfunction "NRST_7") (pintype "bidirectional"))
    )
    (net (code "51") (name "Net-(U1A-PH0-OSC_IN)") (class "Default")
      (node (ref "C9") (pin "2") (pinfunction "2_2") (pintype "input"))
      (node (ref "U1") (pin "5") (pinfunction "PH0-OSC_IN_5") (pintype "bidirectional"))
      (node (ref "X1") (pin "1") (pinfunction "OSC1_1") (pintype "input"))
    )
    (net (code "52") (name "Net-(U1A-PH1-OSC_OUT)") (class "Default")
      (node (ref "C10") (pin "2") (pinfunction "2_2") (pintype "input"))
      (node (ref "U1") (pin "6") (pinfunction "PH1-OSC_OUT_6") (pintype "bidirectional"))
      (node (ref "X1") (pin "3") (pinfunction "OSC2_3") (pintype "input"))
    )
    (net (code "53") (name "Net-(U1A-VCAP1)") (class "Default")
      (node (ref "C2") (pin "2") (pinfunction "2_2") (pintype "input"))
      (node (ref "U1") (pin "22") (pinfunction "VCAP1_22") (pintype "input"))
    )
    (net (code "54") (name "Net-(U1B-VDDA{slash}VREF+)") (class "Default")
      (node (ref "C7") (pin "2") (pinfunction "2_2") (pintype "input"))
      (node (ref "C8") (pin "2") (pinfunction "2_2") (pintype "input"))
      (node (ref "R17") (pin "1") (pinfunction "1_1") (pintype "input"))
      (node (ref "U1") (pin "9") (pinfunction "VDDA/VREF+_9") (pintype "input"))
    )
    (net (code "55") (name "Net-(U3-FB)") (class "Default")
      (node (ref "R14") (pin "1") (pinfunction "1_1") (pintype "unspecified"))
      (node (ref "U3") (pin "8") (pinfunction "FB_8") (pintype "input"))
    )
    (net (code "56") (name "Net-(U3-ISET)") (class "Default")
      (node (ref "R12") (pin "2") (pinfunction "2_2") (pintype "input"))
      (node (ref "U3") (pin "2") (pinfunction "ISET_2") (pintype "input"))
    )
    (net (code "57") (name "Net-(U9-FB)") (class "Default")
      (node (ref "R10") (pin "2") (pinfunction "2_2") (pintype "input"))
      (node (ref "R9") (pin "1") (pinfunction "1_1") (pintype "input"))
      (node (ref "U9") (pin "3") (pinfunction "FB_3") (pintype "input"))
    )
    (net (code "58") (name "unconnected-(U3-DONE#-Pad6)") (class "Default")
      (node (ref "U3") (pin "6") (pinfunction "DONE#_6") (pintype "input+no_connect"))
    )
    (net (code "59") (name "unconnected-(U9-PG-Pad14)") (class "Default")
      (node (ref "U9") (pin "14") (pinfunction "PG_14") (pintype "input+no_connect"))
    )
    (net (code "60") (name "unconnected-(USB2-CC1-PadA5)") (class "Default")
      (node (ref "USB2") (pin "A5") (pinfunction "CC1_A5") (pintype "input+no_connect"))
    )
    (net (code "61") (name "unconnected-(USB2-CC2-PadB5)") (class "Default")
      (node (ref "USB2") (pin "B5") (pinfunction "CC2_B5") (pintype "input+no_connect"))
    )
    (net (code "62") (name "unconnected-(USB2-SBU1-PadA8)") (class "Default")
      (node (ref "USB2") (pin "A8") (pinfunction "SBU1_A8") (pintype "input+no_connect"))
    )
    (net (code "63") (name "unconnected-(USB2-SBU2-PadB8)") (class "Default")
      (node (ref "USB2") (pin "B8") (pinfunction "SBU2_B8") (pintype "input+no_connect"))
    )
  )
)
